# product.net
KiCad netlist of a schematic drawn in EAGLE
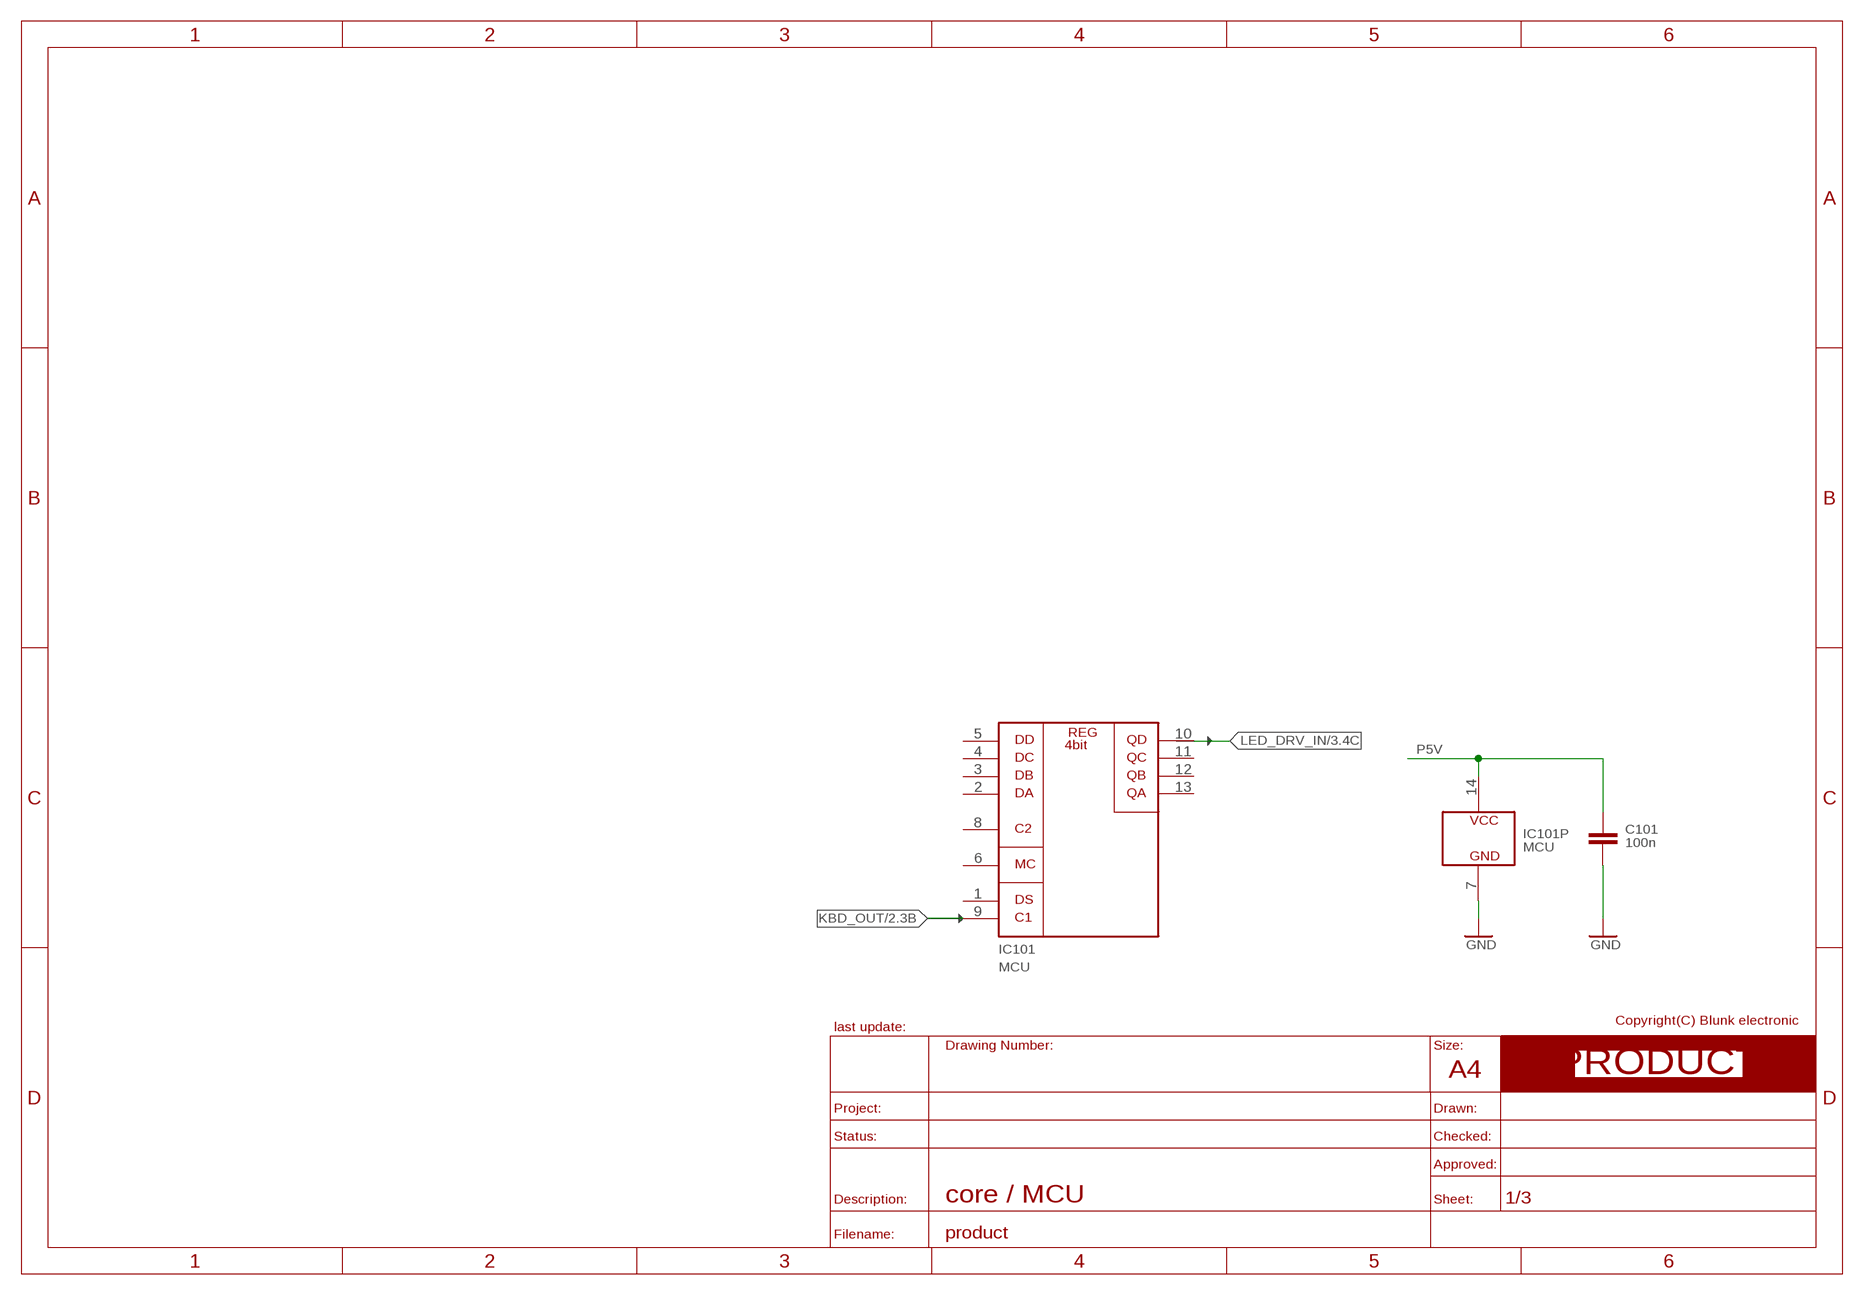
[diagram p0: schematic, sheet 1]
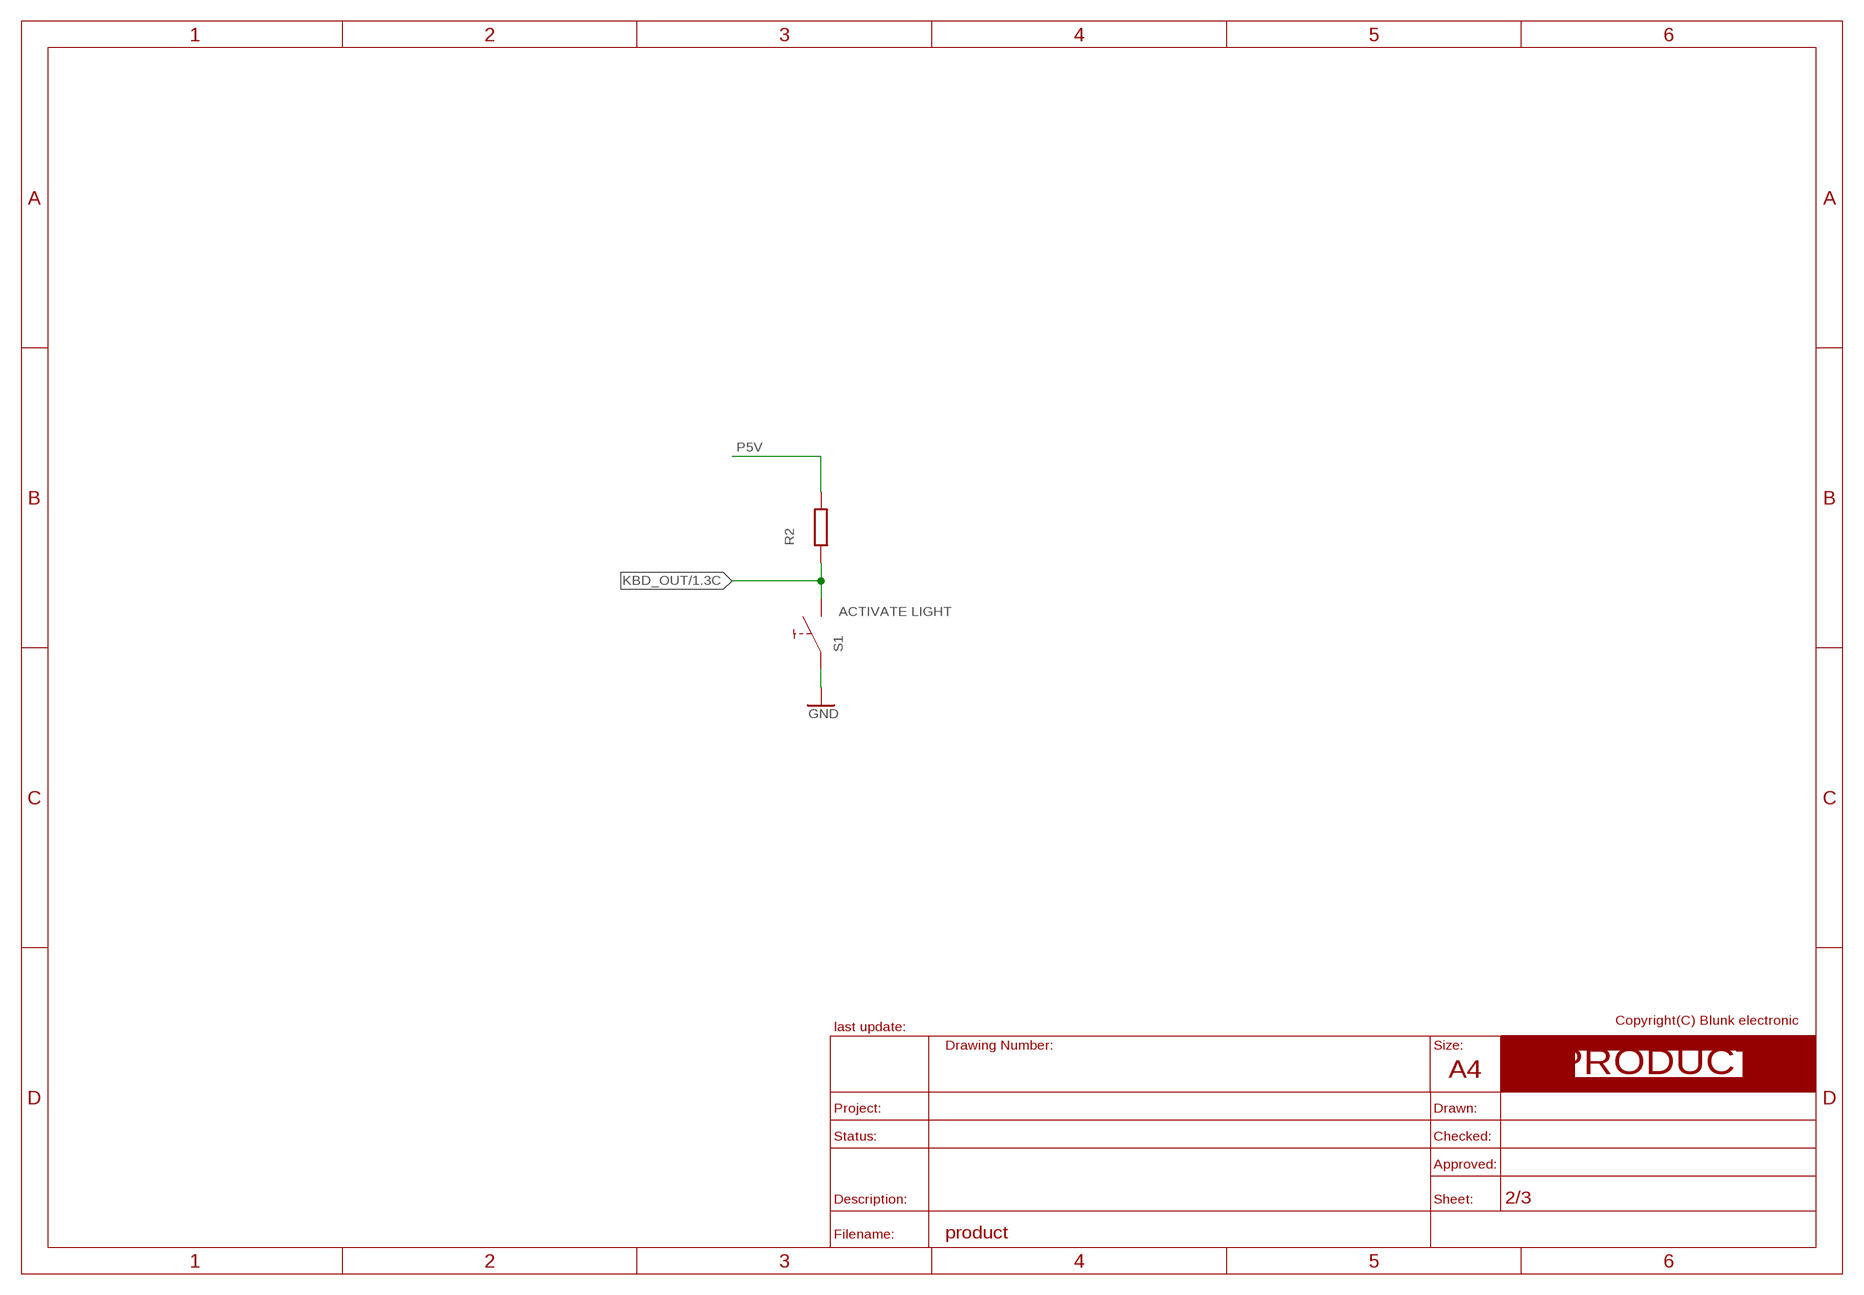
[diagram p1: schematic, sheet 2]
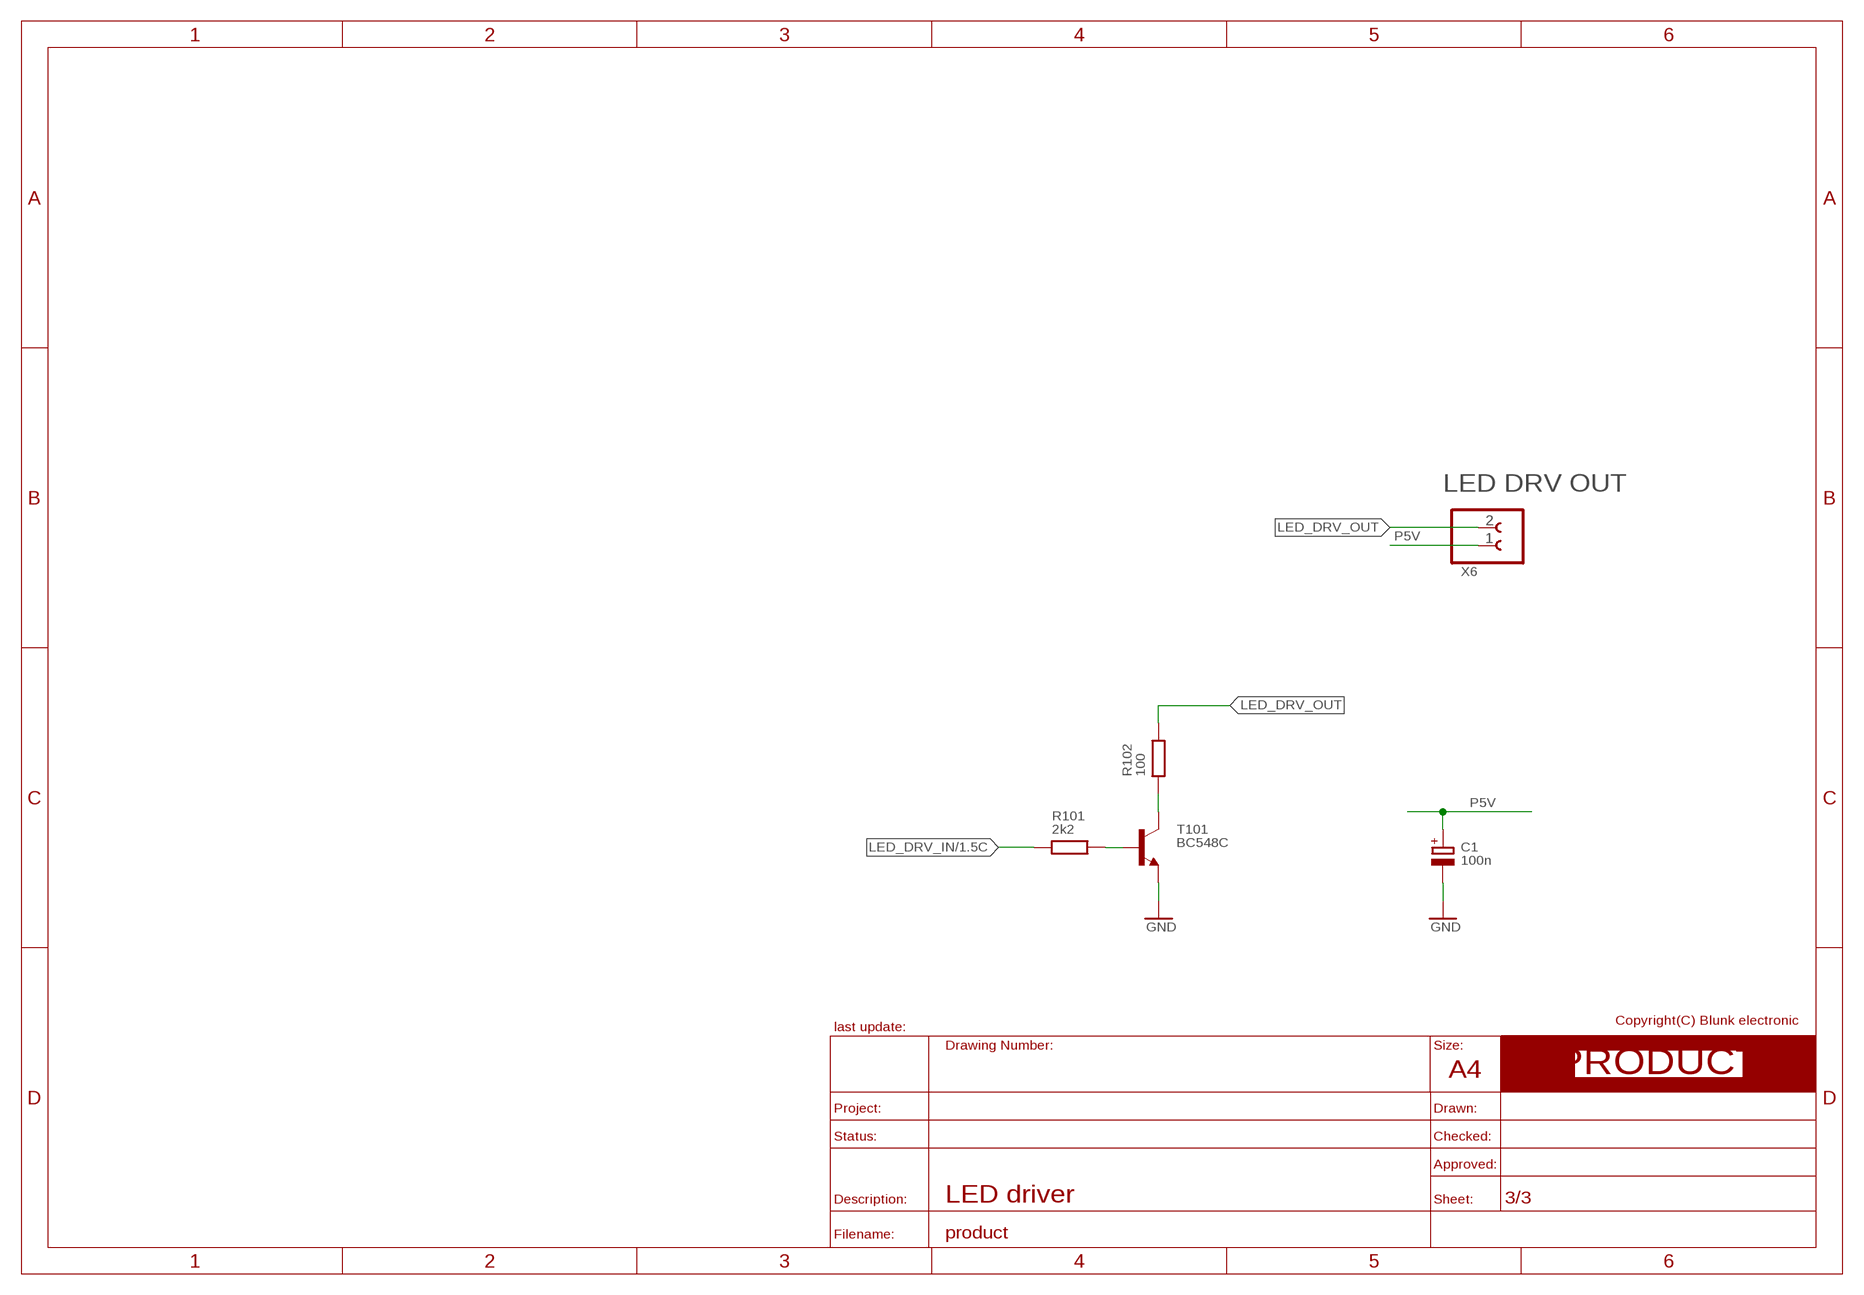
[diagram p2: schematic, sheet 3]

(export (version "E")
  (design (tool "Eeschema 10.0.6"))
  (components
    (comp (ref "C101")
      (value "100n")
      (footprint "eagle-import:S_0603")
      (libsource (lib "eagle-import") (part "C_S_0603"))
    )
    (comp (ref "IC101")
      (value "MCU")
      (footprint "eagle-import:S_SO14")
      (libsource (lib "eagle-import") (part "7495D"))
    )
    (comp (ref "R2")
      (value "R_S_0603")
      (footprint "eagle-import:S_0603")
      (libsource (lib "eagle-import") (part "R_S_0603"))
    )
    (comp (ref "S1")
      (value "PUSH_BUTTON_S_6X6MM")
      (footprint "eagle-import:S_PUSH_BUTTON_6X6")
      (fields (field (name "FUNCTION") "ACTIVATE LIGHT"))
      (libsource (lib "eagle-import") (part "PUSH_BUTTON_S_6X6MM"))
    )
    (comp (ref "C1")
      (value "100n")
      (footprint "eagle-import:S_3216-18")
      (libsource (lib "eagle-import") (part "C_POL_S_3216-18"))
    )
    (comp (ref "R101")
      (value "2k2")
      (footprint "eagle-import:S_0603")
      (libsource (lib "eagle-import") (part "R_S_0603"))
    )
    (comp (ref "R102")
      (value "100")
      (footprint "eagle-import:S_0603")
      (libsource (lib "eagle-import") (part "R_S_0603"))
    )
    (comp (ref "T101")
      (value "BC548C")
      (footprint "eagle-import:S_SOT23")
      (libsource (lib "eagle-import") (part "NPN_S_SOT23"))
    )
    (comp (ref "X6")
      (value "CLAMP_1X2-T-2.5MM")
      (footprint "eagle-import:T_WIRE_CLAMP_1X2_PITCH_2MM5")
      (fields (field (name "FUNCTION") "LED DRV OUT"))
      (libsource (lib "eagle-import") (part "CLAMP_1X2-T-2.5MM"))
    )
  )
  (nets
    (net (code "1") (name "GND") (class "Default")
      (node (ref "C1") (pin "-") (pinfunction "-_-") (pintype "passive"))
      (node (ref "C101") (pin "2") (pinfunction "2_2") (pintype "passive"))
      (node (ref "IC101") (pin "7") (pinfunction "GND_7") (pintype "power_in"))
      (node (ref "S1") (pin "A") (pinfunction "A1_A") (pintype "passive"))
      (node (ref "S1") (pin "A1") (pinfunction "A1_A1") (pintype "passive"))
      (node (ref "T101") (pin "2") (pinfunction "E_2") (pintype "passive"))
    )
    (net (code "2") (name "KBD_OUT") (class "Default")
      (node (ref "IC101") (pin "9") (pinfunction "C1_9") (pintype "input"))
      (node (ref "R2") (pin "1") (pinfunction "1_1") (pintype "passive"))
      (node (ref "S1") (pin "B") (pinfunction "B1_B") (pintype "passive"))
      (node (ref "S1") (pin "B1") (pinfunction "B1_B1") (pintype "passive"))
    )
    (net (code "3") (name "LED_DRV_IN") (class "Default")
      (node (ref "IC101") (pin "10") (pinfunction "QD_10") (pintype "output"))
      (node (ref "R101") (pin "1") (pinfunction "1_1") (pintype "passive"))
    )
    (net (code "4") (name "LED_DRV_OUT") (class "Default")
      (node (ref "R102") (pin "2") (pinfunction "2_2") (pintype "passive"))
      (node (ref "X6") (pin "2") (pinfunction "2_2") (pintype "passive"))
    )
    (net (code "5") (name "Net-(T101-B)") (class "Default")
      (node (ref "R101") (pin "2") (pinfunction "2_2") (pintype "passive"))
      (node (ref "T101") (pin "1") (pinfunction "B_1") (pintype "passive"))
    )
    (net (code "6") (name "Net-(T101-C)") (class "Default")
      (node (ref "R102") (pin "1") (pinfunction "1_1") (pintype "passive"))
      (node (ref "T101") (pin "3") (pinfunction "C_3") (pintype "passive"))
    )
    (net (code "7") (name "P5V") (class "Default")
      (node (ref "C1") (pin "+") (pinfunction "+_+") (pintype "passive"))
      (node (ref "C101") (pin "1") (pinfunction "1_1") (pintype "passive"))
      (node (ref "IC101") (pin "14") (pinfunction "VCC_14") (pintype "power_in"))
      (node (ref "R2") (pin "2") (pinfunction "2_2") (pintype "passive"))
      (node (ref "X6") (pin "1") (pinfunction "1_1") (pintype "passive"))
    )
    (net (code "8") (name "unconnected-(IC101A-C2-Pad8)") (class "Default")
      (node (ref "IC101") (pin "8") (pinfunction "C2_8") (pintype "input"))
    )
    (net (code "9") (name "unconnected-(IC101A-DA-Pad2)") (class "Default")
      (node (ref "IC101") (pin "2") (pinfunction "DA_2") (pintype "input"))
    )
    (net (code "10") (name "unconnected-(IC101A-DB-Pad3)") (class "Default")
      (node (ref "IC101") (pin "3") (pinfunction "DB_3") (pintype "input"))
    )
    (net (code "11") (name "unconnected-(IC101A-DC-Pad4)") (class "Default")
      (node (ref "IC101") (pin "4") (pinfunction "DC_4") (pintype "input"))
    )
    (net (code "12") (name "unconnected-(IC101A-DD-Pad5)") (class "Default")
      (node (ref "IC101") (pin "5") (pinfunction "DD_5") (pintype "input"))
    )
    (net (code "13") (name "unconnected-(IC101A-DS-Pad1)") (class "Default")
      (node (ref "IC101") (pin "1") (pinfunction "DS_1") (pintype "input"))
    )
    (net (code "14") (name "unconnected-(IC101A-MC-Pad6)") (class "Default")
      (node (ref "IC101") (pin "6") (pinfunction "MC_6") (pintype "input"))
    )
    (net (code "15") (name "unconnected-(IC101A-QA-Pad13)") (class "Default")
      (node (ref "IC101") (pin "13") (pinfunction "QA_13") (pintype "output"))
    )
    (net (code "16") (name "unconnected-(IC101A-QB-Pad12)") (class "Default")
      (node (ref "IC101") (pin "12") (pinfunction "QB_12") (pintype "output"))
    )
    (net (code "17") (name "unconnected-(IC101A-QC-Pad11)") (class "Default")
      (node (ref "IC101") (pin "11") (pinfunction "QC_11") (pintype "output"))
    )
  )
)
